# IO.net
KiCad netlist of a schematic drawn in Altium Designer
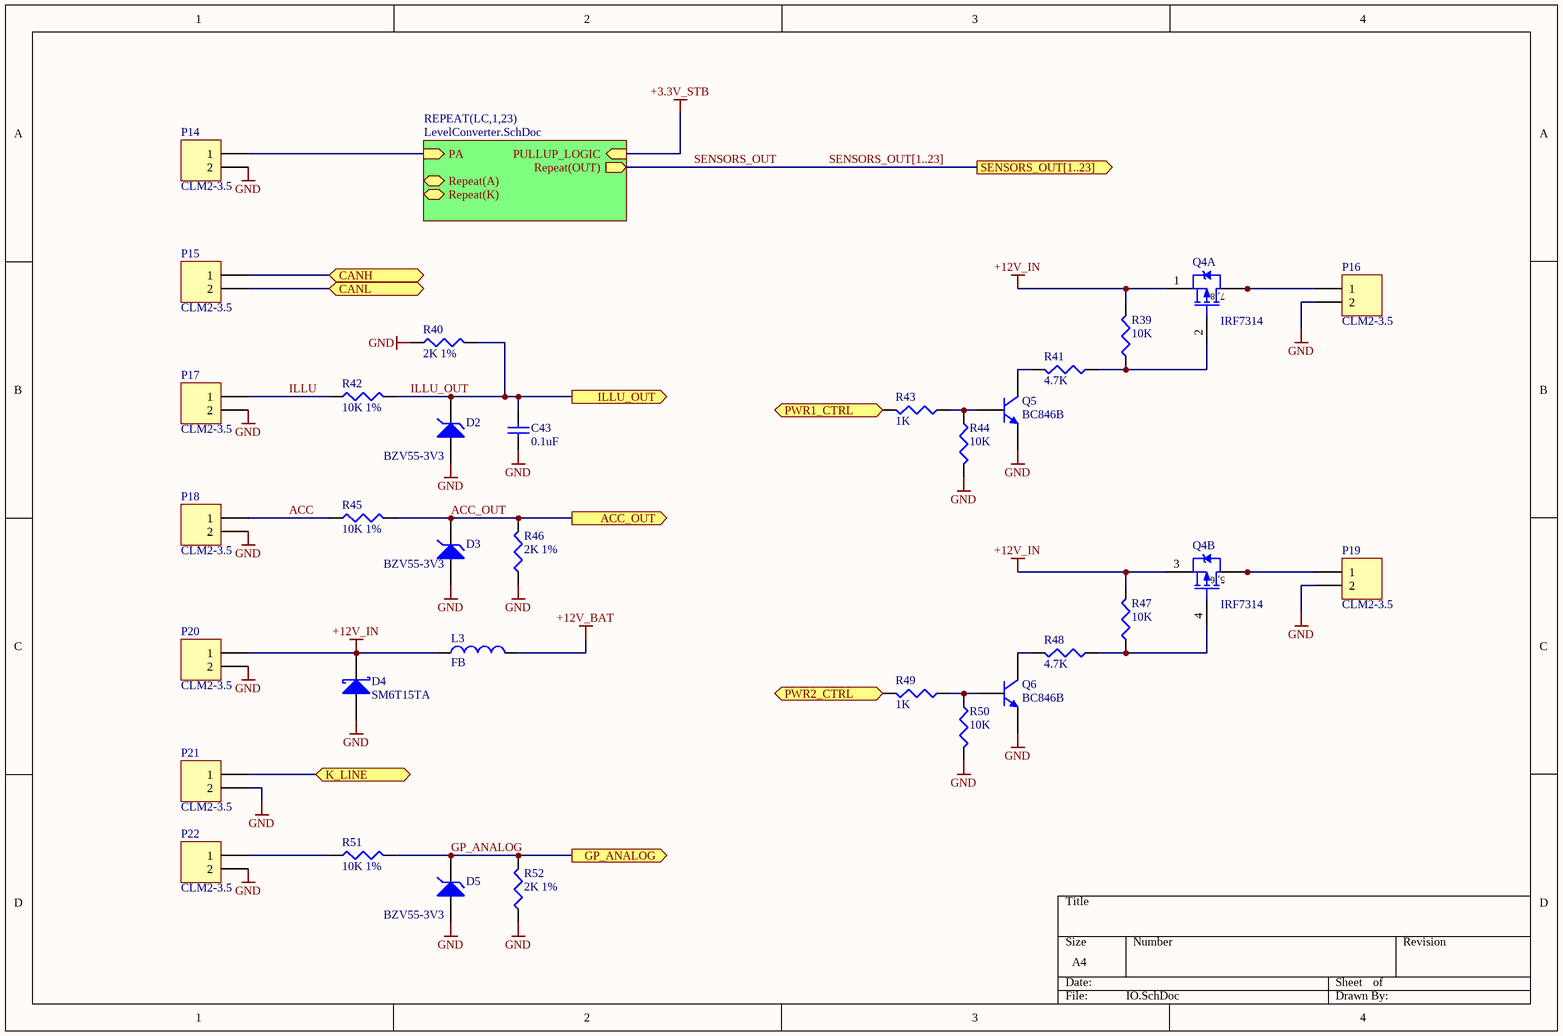
[diagram p0: IO.SchDoc]

(export (version "E")
  (design (tool "Eeschema 10.0.6"))
  (components
    (comp (ref "C43")
      (value "0.1uF")
      (footprint "2012[0805]")
      (description "Ceramic Chip Capacitor - Standard")
      (fields (field (name "PUBLISHER") "Altium Limited"))
      (libsource (lib "ResAndCaps") (part "C0805"))
    )
    (comp (ref "D2")
      (value "BZV55-3V3")
      (footprint "IPC-SM-782 Section 8.5 MELF:SOD-80/MLL34")
      (description "Zener Diode")
      (fields (field (name "PUBLISHER") "Altium Limited"))
      (libsource (lib "Miscellaneous Devices") (part "D Zener"))
    )
    (comp (ref "D3")
      (value "BZV55-3V3")
      (footprint "IPC-SM-782 Section 8.5 MELF:SOD-80/MLL34")
      (description "Zener Diode")
      (fields (field (name "PUBLISHER") "Altium Limited"))
      (libsource (lib "Miscellaneous Devices") (part "D Zener"))
    )
    (comp (ref "D4")
      (value "SM6T15TA")
      (footprint "SMB")
      (fields (field (name "PUBLISHER") "Altium Limited"))
      (libsource (lib "Miscellaneous Devices") (part "D Schottky"))
    )
    (comp (ref "D5")
      (value "BZV55-3V3")
      (footprint "IPC-SM-782 Section 8.5 MELF:SOD-80/MLL34")
      (description "Zener Diode")
      (fields (field (name "PUBLISHER") "Altium Limited"))
      (libsource (lib "Miscellaneous Devices") (part "D Zener"))
    )
    (comp (ref "L3")
      (value "FB")
      (footprint "INDC4516AN")
      (description "BLM41PG600SN1L")
      (fields (field (name "PUBLISHER") "Altium Limited"))
      (libsource (lib "Miscellaneous Devices") (part "Inductor"))
    )
    (comp (ref "P14")
      (value "CLM2-3.5")
      (footprint "CLM2-3.5")
      (libsource (lib "connectors") (part "CLM2-3.5"))
    )
    (comp (ref "P15")
      (value "CLM2-3.5")
      (footprint "CLM2-3.5")
      (libsource (lib "connectors") (part "CLM2-3.5"))
    )
    (comp (ref "P16") (value "CLM2-3.5") (footprint "CLM2-3.5") (libsource (lib "") (part "CLM2-3.5_1")))
    (comp (ref "P17")
      (value "CLM2-3.5")
      (footprint "CLM2-3.5")
      (libsource (lib "connectors") (part "CLM2-3.5"))
    )
    (comp (ref "P18")
      (value "CLM2-3.5")
      (footprint "CLM2-3.5")
      (libsource (lib "connectors") (part "CLM2-3.5"))
    )
    (comp (ref "P19") (value "CLM2-3.5") (footprint "CLM2-3.5") (libsource (lib "") (part "CLM2-3.5_1")))
    (comp (ref "P20")
      (value "CLM2-3.5")
      (footprint "CLM2-3.5")
      (libsource (lib "connectors") (part "CLM2-3.5"))
    )
    (comp (ref "P21")
      (value "CLM2-3.5")
      (footprint "CLM2-3.5")
      (libsource (lib "connectors") (part "CLM2-3.5"))
    )
    (comp (ref "P22")
      (value "CLM2-3.5")
      (footprint "CLM2-3.5")
      (libsource (lib "connectors") (part "CLM2-3.5"))
    )
    (comp (ref "Q4")
      (value "IRF7314")
      (footprint "SO-8_N")
      (description "HEXFET Power MOSFET")
      (fields (field (name "PUBLISHER") "Altium Limited"))
      (libsource (lib "IR Discrete MOSFET - Power") (part "IRF7314"))
    )
    (comp (ref "Q5")
      (value "BC846B")
      (footprint "SOT23_N")
      (description "NPN General-purpose Transistor")
      (fields (field (name "PUBLISHER") "Altium Limited"))
      (libsource (lib "Philips Discrete BJT - Low Power") (part "BC846B"))
    )
    (comp (ref "Q6")
      (value "BC846B")
      (footprint "SOT23_N")
      (description "NPN General-purpose Transistor")
      (fields (field (name "PUBLISHER") "Altium Limited"))
      (libsource (lib "Philips Discrete BJT - Low Power") (part "BC846B"))
    )
    (comp (ref "R39")
      (value "10K")
      (footprint "R2012[0805]")
      (description "R0805")
      (fields (field (name "PUBLISHER") "Altium Limited"))
      (libsource (lib "ResAndCaps") (part "R0805"))
    )
    (comp (ref "R40")
      (value "2K 1%")
      (footprint "R2012[0805]")
      (description "R0805")
      (fields (field (name "PUBLISHER") "Altium Limited"))
      (libsource (lib "ResAndCaps") (part "R0805"))
    )
    (comp (ref "R41")
      (value "4.7K")
      (footprint "R2012[0805]")
      (description "R0805")
      (fields (field (name "PUBLISHER") "Altium Limited"))
      (libsource (lib "ResAndCaps") (part "R0805"))
    )
    (comp (ref "R42")
      (value "10K 1%")
      (footprint "R2012[0805]")
      (description "R0805")
      (fields (field (name "PUBLISHER") "Altium Limited"))
      (libsource (lib "ResAndCaps") (part "R0805"))
    )
    (comp (ref "R43")
      (value "1K")
      (footprint "R2012[0805]")
      (description "R0805")
      (fields (field (name "PUBLISHER") "Altium Limited"))
      (libsource (lib "ResAndCaps") (part "R0805"))
    )
    (comp (ref "R44")
      (value "10K")
      (footprint "R2012[0805]")
      (description "R0805")
      (fields (field (name "PUBLISHER") "Altium Limited"))
      (libsource (lib "ResAndCaps") (part "R0805"))
    )
    (comp (ref "R45")
      (value "10K 1%")
      (footprint "R2012[0805]")
      (description "R0805")
      (fields (field (name "PUBLISHER") "Altium Limited"))
      (libsource (lib "ResAndCaps") (part "R0805"))
    )
    (comp (ref "R46")
      (value "2K 1%")
      (footprint "R2012[0805]")
      (description "R0805")
      (fields (field (name "PUBLISHER") "Altium Limited"))
      (libsource (lib "ResAndCaps") (part "R0805"))
    )
    (comp (ref "R47")
      (value "10K")
      (footprint "R2012[0805]")
      (description "R0805")
      (fields (field (name "PUBLISHER") "Altium Limited"))
      (libsource (lib "ResAndCaps") (part "R0805"))
    )
    (comp (ref "R48")
      (value "4.7K")
      (footprint "R2012[0805]")
      (description "R0805")
      (fields (field (name "PUBLISHER") "Altium Limited"))
      (libsource (lib "ResAndCaps") (part "R0805"))
    )
    (comp (ref "R49")
      (value "1K")
      (footprint "R2012[0805]")
      (description "R0805")
      (fields (field (name "PUBLISHER") "Altium Limited"))
      (libsource (lib "ResAndCaps") (part "R0805"))
    )
    (comp (ref "R50")
      (value "10K")
      (footprint "R2012[0805]")
      (description "R0805")
      (fields (field (name "PUBLISHER") "Altium Limited"))
      (libsource (lib "ResAndCaps") (part "R0805"))
    )
    (comp (ref "R51")
      (value "10K 1%")
      (footprint "R2012[0805]")
      (description "R0805")
      (fields (field (name "PUBLISHER") "Altium Limited"))
      (libsource (lib "ResAndCaps") (part "R0805"))
    )
    (comp (ref "R52")
      (value "2K 1%")
      (footprint "R2012[0805]")
      (description "R0805")
      (fields (field (name "PUBLISHER") "Altium Limited"))
      (libsource (lib "ResAndCaps") (part "R0805"))
    )
  )
  (nets
    (net (code "25") (name "+12V_BAT") (class "Default")
      (node (ref "L3") (pin "2") (pinfunction "2_2") (pintype "passive"))
    )
    (net (code "26") (name "+12V_IN") (class "Default")
      (node (ref "D4") (pin "2") (pinfunction "K_2") (pintype "passive"))
      (node (ref "L3") (pin "1") (pinfunction "1_1") (pintype "passive"))
      (node (ref "P20") (pin "1") (pinfunction "1_1") (pintype "passive"))
      (node (ref "Q4") (pin "1") (pinfunction "S_1") (pintype "passive"))
      (node (ref "Q4") (pin "3") (pinfunction "S_3") (pintype "passive"))
      (node (ref "R39") (pin "2") (pinfunction "2_2") (pintype "passive"))
      (node (ref "R47") (pin "2") (pinfunction "2_2") (pintype "passive"))
    )
    (net (code "27") (name "/ACC") (class "Default")
      (node (ref "P18") (pin "1") (pinfunction "1_1") (pintype "passive"))
      (node (ref "R45") (pin "2") (pinfunction "2_2") (pintype "passive"))
    )
    (net (code "28") (name "/ACC_OUT") (class "Default")
      (node (ref "D3") (pin "2") (pinfunction "K_2") (pintype "passive"))
      (node (ref "R45") (pin "1") (pinfunction "1_1") (pintype "passive"))
      (node (ref "R46") (pin "1") (pinfunction "1_1") (pintype "passive"))
    )
    (net (code "29") (name "/CANH") (class "Default")
      (node (ref "P15") (pin "1") (pinfunction "1_1") (pintype "passive"))
    )
    (net (code "30") (name "/CANL") (class "Default")
      (node (ref "P15") (pin "2") (pinfunction "2_2") (pintype "passive"))
    )
    (net (code "31") (name "/GP_ANALOG") (class "Default")
      (node (ref "D5") (pin "2") (pinfunction "K_2") (pintype "passive"))
      (node (ref "R51") (pin "1") (pinfunction "1_1") (pintype "passive"))
      (node (ref "R52") (pin "1") (pinfunction "1_1") (pintype "passive"))
    )
    (net (code "32") (name "/ILLU") (class "Default")
      (node (ref "P17") (pin "1") (pinfunction "1_1") (pintype "passive"))
      (node (ref "R42") (pin "2") (pinfunction "2_2") (pintype "passive"))
    )
    (net (code "33") (name "/ILLU_OUT") (class "Default")
      (node (ref "C43") (pin "2") (pinfunction "2_2") (pintype "passive"))
      (node (ref "D2") (pin "2") (pinfunction "K_2") (pintype "passive"))
      (node (ref "R40") (pin "1") (pinfunction "1_1") (pintype "passive"))
      (node (ref "R42") (pin "1") (pinfunction "1_1") (pintype "passive"))
    )
    (net (code "34") (name "/K_LINE") (class "Default")
      (node (ref "P21") (pin "1") (pinfunction "1_1") (pintype "passive"))
    )
    (net (code "35") (name "/PA") (class "Default")
      (node (ref "P14") (pin "1") (pinfunction "1_1") (pintype "passive"))
    )
    (net (code "36") (name "/PWR1_CTRL") (class "Default")
      (node (ref "R43") (pin "2") (pinfunction "2_2") (pintype "passive"))
    )
    (net (code "37") (name "/PWR2_CTRL") (class "Default")
      (node (ref "R49") (pin "2") (pinfunction "2_2") (pintype "passive"))
    )
    (net (code "42") (name "GND") (class "Default")
      (node (ref "C43") (pin "1") (pinfunction "1_1") (pintype "passive"))
      (node (ref "D2") (pin "1") (pinfunction "A_1") (pintype "passive"))
      (node (ref "D3") (pin "1") (pinfunction "A_1") (pintype "passive"))
      (node (ref "D4") (pin "1") (pinfunction "A_1") (pintype "passive"))
      (node (ref "D5") (pin "1") (pinfunction "A_1") (pintype "passive"))
      (node (ref "P14") (pin "2") (pinfunction "2_2") (pintype "passive"))
      (node (ref "P16") (pin "2") (pinfunction "2_2") (pintype "passive"))
      (node (ref "P17") (pin "2") (pinfunction "2_2") (pintype "passive"))
      (node (ref "P18") (pin "2") (pinfunction "2_2") (pintype "passive"))
      (node (ref "P19") (pin "2") (pinfunction "2_2") (pintype "passive"))
      (node (ref "P20") (pin "2") (pinfunction "2_2") (pintype "passive"))
      (node (ref "P21") (pin "2") (pinfunction "2_2") (pintype "passive"))
      (node (ref "P22") (pin "2") (pinfunction "2_2") (pintype "passive"))
      (node (ref "Q5") (pin "2") (pinfunction "E_2") (pintype "passive"))
      (node (ref "Q6") (pin "2") (pinfunction "E_2") (pintype "passive"))
      (node (ref "R40") (pin "2") (pinfunction "2_2") (pintype "passive"))
      (node (ref "R44") (pin "2") (pinfunction "2_2") (pintype "passive"))
      (node (ref "R46") (pin "2") (pinfunction "2_2") (pintype "passive"))
      (node (ref "R50") (pin "2") (pinfunction "2_2") (pintype "passive"))
      (node (ref "R52") (pin "2") (pinfunction "2_2") (pintype "passive"))
    )
    (net (code "43") (name "Net-(P16-Pad1)") (class "Default")
      (node (ref "P16") (pin "1") (pinfunction "1_1") (pintype "passive"))
      (node (ref "Q4") (pin "7") (pinfunction "D_7") (pintype "passive"))
      (node (ref "Q4") (pin "8") (pinfunction "D_8") (pintype "passive"))
    )
    (net (code "44") (name "Net-(P19-Pad1)") (class "Default")
      (node (ref "P19") (pin "1") (pinfunction "1_1") (pintype "passive"))
      (node (ref "Q4") (pin "5") (pinfunction "D_5") (pintype "passive"))
      (node (ref "Q4") (pin "6") (pinfunction "D_6") (pintype "passive"))
    )
    (net (code "45") (name "Net-(P22-Pad1)") (class "Default")
      (node (ref "P22") (pin "1") (pinfunction "1_1") (pintype "passive"))
      (node (ref "R51") (pin "2") (pinfunction "2_2") (pintype "passive"))
    )
    (net (code "46") (name "Net-(Q4A-G)") (class "Default")
      (node (ref "Q4") (pin "2") (pinfunction "G_2") (pintype "passive"))
      (node (ref "R39") (pin "1") (pinfunction "1_1") (pintype "passive"))
      (node (ref "R41") (pin "1") (pinfunction "1_1") (pintype "passive"))
    )
    (net (code "47") (name "Net-(Q4B-G)") (class "Default")
      (node (ref "Q4") (pin "4") (pinfunction "G_4") (pintype "passive"))
      (node (ref "R47") (pin "1") (pinfunction "1_1") (pintype "passive"))
      (node (ref "R48") (pin "1") (pinfunction "1_1") (pintype "passive"))
    )
    (net (code "48") (name "Net-(Q5-B)") (class "Default")
      (node (ref "Q5") (pin "1") (pinfunction "B_1") (pintype "passive"))
      (node (ref "R43") (pin "1") (pinfunction "1_1") (pintype "passive"))
      (node (ref "R44") (pin "1") (pinfunction "1_1") (pintype "passive"))
    )
    (net (code "49") (name "Net-(Q5-C)") (class "Default")
      (node (ref "Q5") (pin "3") (pinfunction "C_3") (pintype "passive"))
      (node (ref "R41") (pin "2") (pinfunction "2_2") (pintype "passive"))
    )
    (net (code "50") (name "Net-(Q6-B)") (class "Default")
      (node (ref "Q6") (pin "1") (pinfunction "B_1") (pintype "passive"))
      (node (ref "R49") (pin "1") (pinfunction "1_1") (pintype "passive"))
      (node (ref "R50") (pin "1") (pinfunction "1_1") (pintype "passive"))
    )
    (net (code "51") (name "Net-(Q6-C)") (class "Default")
      (node (ref "Q6") (pin "3") (pinfunction "C_3") (pintype "passive"))
      (node (ref "R48") (pin "2") (pinfunction "2_2") (pintype "passive"))
    )
  )
)
